# Trace.net
KiCad netlist of a schematic drawn in EAGLE
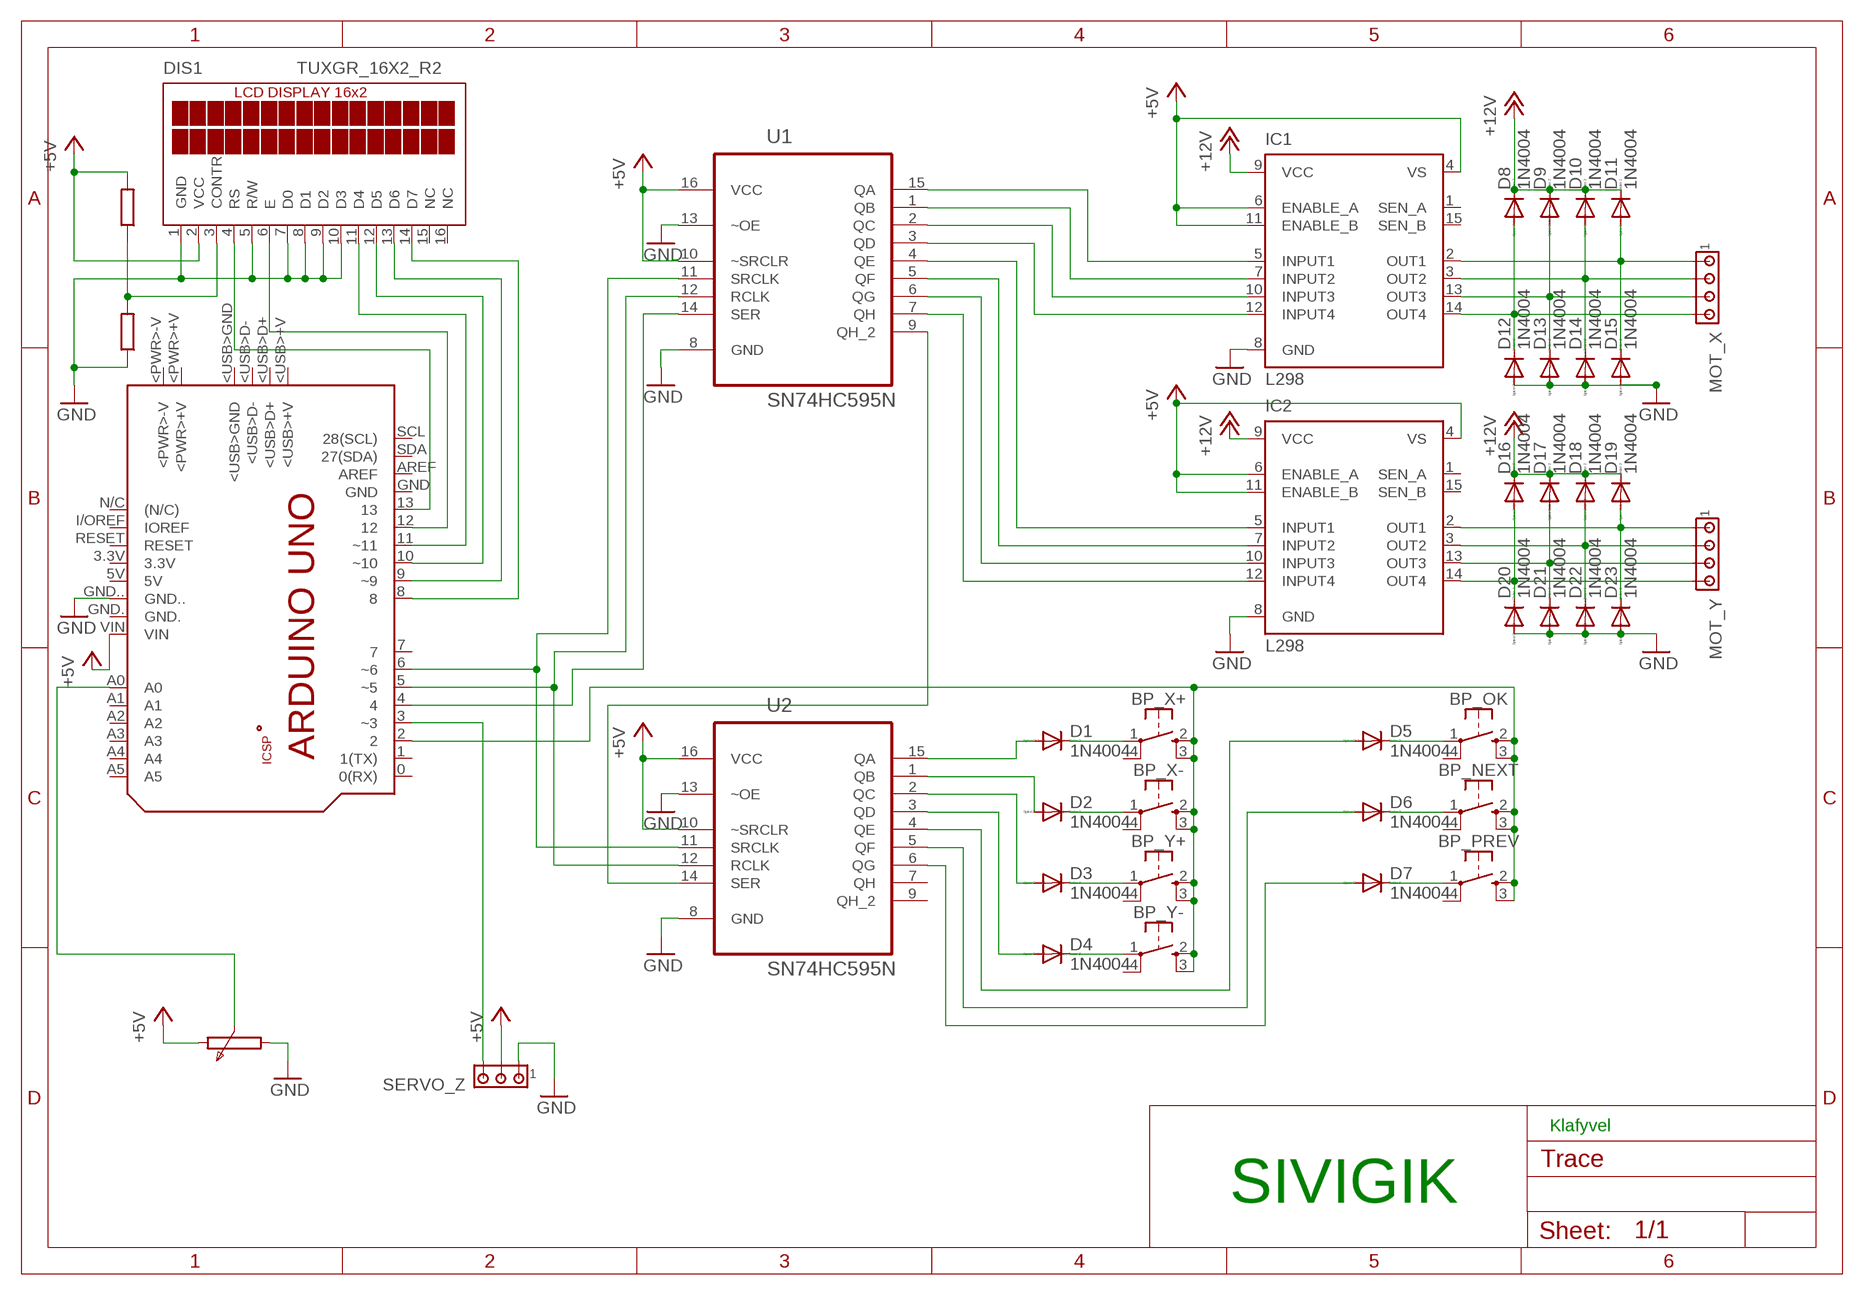
[diagram p0: schematic, sheet 1]

(export (version "E")
  (design (tool "Eeschema 10.0.6"))
  (components
    (comp (ref "BP_NEXT")
      (value "SW-TACTILE-TL3315")
      (footprint "eagle-import:SW_TL3315N")
      (libsource (lib "eagle-import") (part "SW-TACTILE-TL3315"))
    )
    (comp (ref "BP_OK")
      (value "SW-TACTILE-TL3315")
      (footprint "eagle-import:SW_TL3315N")
      (libsource (lib "eagle-import") (part "SW-TACTILE-TL3315"))
    )
    (comp (ref "BP_PREV")
      (value "SW-TACTILE-TL3315")
      (footprint "eagle-import:SW_TL3315N")
      (libsource (lib "eagle-import") (part "SW-TACTILE-TL3315"))
    )
    (comp (ref "BP_X+")
      (value "SW-TACTILE-TL3315")
      (footprint "eagle-import:SW_TL3315N")
      (libsource (lib "eagle-import") (part "SW-TACTILE-TL3315"))
    )
    (comp (ref "BP_X-")
      (value "SW-TACTILE-TL3315")
      (footprint "eagle-import:SW_TL3315N")
      (libsource (lib "eagle-import") (part "SW-TACTILE-TL3315"))
    )
    (comp (ref "BP_Y+")
      (value "SW-TACTILE-TL3315")
      (footprint "eagle-import:SW_TL3315N")
      (libsource (lib "eagle-import") (part "SW-TACTILE-TL3315"))
    )
    (comp (ref "BP_Y-")
      (value "SW-TACTILE-TL3315")
      (footprint "eagle-import:SW_TL3315N")
      (libsource (lib "eagle-import") (part "SW-TACTILE-TL3315"))
    )
    (comp (ref "D1")
      (value "1N4004")
      (footprint "eagle-import:DO41-10")
      (libsource (lib "eagle-import") (part "1N4004"))
    )
    (comp (ref "D2")
      (value "1N4004")
      (footprint "eagle-import:DO41-10")
      (libsource (lib "eagle-import") (part "1N4004"))
    )
    (comp (ref "D3")
      (value "1N4004")
      (footprint "eagle-import:DO41-10")
      (libsource (lib "eagle-import") (part "1N4004"))
    )
    (comp (ref "D4")
      (value "1N4004")
      (footprint "eagle-import:DO41-10")
      (libsource (lib "eagle-import") (part "1N4004"))
    )
    (comp (ref "D5")
      (value "1N4004")
      (footprint "eagle-import:DO41-10")
      (libsource (lib "eagle-import") (part "1N4004"))
    )
    (comp (ref "D6")
      (value "1N4004")
      (footprint "eagle-import:DO41-10")
      (libsource (lib "eagle-import") (part "1N4004"))
    )
    (comp (ref "D7")
      (value "1N4004")
      (footprint "eagle-import:DO41-10")
      (libsource (lib "eagle-import") (part "1N4004"))
    )
    (comp (ref "D8")
      (value "1N4004")
      (footprint "eagle-import:DO41-10")
      (libsource (lib "eagle-import") (part "1N4004"))
    )
    (comp (ref "D9")
      (value "1N4004")
      (footprint "eagle-import:DO41-10")
      (libsource (lib "eagle-import") (part "1N4004"))
    )
    (comp (ref "D10")
      (value "1N4004")
      (footprint "eagle-import:DO41-10")
      (libsource (lib "eagle-import") (part "1N4004"))
    )
    (comp (ref "D11")
      (value "1N4004")
      (footprint "eagle-import:DO41-10")
      (libsource (lib "eagle-import") (part "1N4004"))
    )
    (comp (ref "D12")
      (value "1N4004")
      (footprint "eagle-import:DO41-10")
      (libsource (lib "eagle-import") (part "1N4004"))
    )
    (comp (ref "D13")
      (value "1N4004")
      (footprint "eagle-import:DO41-10")
      (libsource (lib "eagle-import") (part "1N4004"))
    )
    (comp (ref "D14")
      (value "1N4004")
      (footprint "eagle-import:DO41-10")
      (libsource (lib "eagle-import") (part "1N4004"))
    )
    (comp (ref "D15")
      (value "1N4004")
      (footprint "eagle-import:DO41-10")
      (libsource (lib "eagle-import") (part "1N4004"))
    )
    (comp (ref "D16")
      (value "1N4004")
      (footprint "eagle-import:DO41-10")
      (libsource (lib "eagle-import") (part "1N4004"))
    )
    (comp (ref "D17")
      (value "1N4004")
      (footprint "eagle-import:DO41-10")
      (libsource (lib "eagle-import") (part "1N4004"))
    )
    (comp (ref "D18")
      (value "1N4004")
      (footprint "eagle-import:DO41-10")
      (libsource (lib "eagle-import") (part "1N4004"))
    )
    (comp (ref "D19")
      (value "1N4004")
      (footprint "eagle-import:DO41-10")
      (libsource (lib "eagle-import") (part "1N4004"))
    )
    (comp (ref "D20")
      (value "1N4004")
      (footprint "eagle-import:DO41-10")
      (libsource (lib "eagle-import") (part "1N4004"))
    )
    (comp (ref "D21")
      (value "1N4004")
      (footprint "eagle-import:DO41-10")
      (libsource (lib "eagle-import") (part "1N4004"))
    )
    (comp (ref "D22")
      (value "1N4004")
      (footprint "eagle-import:DO41-10")
      (libsource (lib "eagle-import") (part "1N4004"))
    )
    (comp (ref "D23")
      (value "1N4004")
      (footprint "eagle-import:DO41-10")
      (libsource (lib "eagle-import") (part "1N4004"))
    )
    (comp (ref "DIS1")
      (value "TUXGR_16X2_R2")
      (footprint "eagle-import:TUXGR_16X2_R2")
      (libsource (lib "eagle-import") (part "TUXGR_16X2_R2"))
    )
    (comp (ref "IC1")
      (value "L298")
      (footprint "eagle-import:MULTIWATT-15")
      (fields (field (name "MPN") "L298N"))
      (libsource (lib "eagle-import") (part "L298"))
    )
    (comp (ref "IC2")
      (value "L298")
      (footprint "eagle-import:MULTIWATT-15")
      (fields (field (name "MPN") "L298N"))
      (libsource (lib "eagle-import") (part "L298"))
    )
    (comp (ref "MOT_X")
      (value "MTA04-100")
      (footprint "eagle-import:10X04MTA")
      (libsource (lib "eagle-import") (part "MTA04-100"))
    )
    (comp (ref "MOT_Y")
      (value "MTA04-100")
      (footprint "eagle-import:10X04MTA")
      (libsource (lib "eagle-import") (part "MTA04-100"))
    )
    (comp (ref "PCB1")
      (value "ARDUINO_UNO")
      (footprint "eagle-import:ARDUINO_UNO")
      (libsource (lib "eagle-import") (part "ARDUINO_UNO"))
    )
    (comp (ref "SERVO_Z")
      (value "MTA03-100")
      (footprint "eagle-import:10X03MTA")
      (libsource (lib "eagle-import") (part "MTA03-100"))
    )
    (comp (ref "U1")
      (value "SN74HC595N")
      (footprint "eagle-import:DIP254P762X508-16")
      (libsource (lib "eagle-import") (part "SN74HC595N"))
    )
    (comp (ref "U2")
      (value "SN74HC595N")
      (footprint "eagle-import:DIP254P762X508-16")
      (libsource (lib "eagle-import") (part "SN74HC595N"))
    )
  )
  (nets
    (net (code "1") (name "+5V") (class "Default")
      (node (ref "DIS1") (pin "2") (pinfunction "VCC_2") (pintype "power_in"))
      (node (ref "IC1") (pin "11") (pinfunction "ENABLE_B_11") (pintype "input"))
      (node (ref "IC1") (pin "4") (pinfunction "VS_4") (pintype "power_in"))
      (node (ref "IC1") (pin "6") (pinfunction "ENABLE_A_6") (pintype "input"))
      (node (ref "IC2") (pin "11") (pinfunction "ENABLE_B_11") (pintype "input"))
      (node (ref "IC2") (pin "4") (pinfunction "VS_4") (pintype "power_in"))
      (node (ref "IC2") (pin "6") (pinfunction "ENABLE_A_6") (pintype "input"))
      (node (ref "PCB1") (pin "VIN") (pinfunction "VIN_VIN") (pintype "bidirectional"))
      (node (ref "SERVO_Z") (pin "2") (pinfunction "2_2") (pintype "passive"))
      (node (ref "U1") (pin "10") (pinfunction "~{SRCLR}_10") (pintype "input"))
      (node (ref "U1") (pin "16") (pinfunction "VCC_16") (pintype "power_in"))
      (node (ref "U2") (pin "10") (pinfunction "~{SRCLR}_10") (pintype "input"))
      (node (ref "U2") (pin "16") (pinfunction "VCC_16") (pintype "power_in"))
    )
    (net (code "2") (name "+12V") (class "Default")
      (node (ref "D10") (pin "C") (pinfunction "C_C") (pintype "passive"))
      (node (ref "D11") (pin "C") (pinfunction "C_C") (pintype "passive"))
      (node (ref "D16") (pin "C") (pinfunction "C_C") (pintype "passive"))
      (node (ref "D17") (pin "C") (pinfunction "C_C") (pintype "passive"))
      (node (ref "D18") (pin "C") (pinfunction "C_C") (pintype "passive"))
      (node (ref "D19") (pin "C") (pinfunction "C_C") (pintype "passive"))
      (node (ref "D8") (pin "C") (pinfunction "C_C") (pintype "passive"))
      (node (ref "D9") (pin "C") (pinfunction "C_C") (pintype "passive"))
      (node (ref "IC1") (pin "9") (pinfunction "VCC_9") (pintype "power_in"))
      (node (ref "IC2") (pin "9") (pinfunction "VCC_9") (pintype "power_in"))
    )
    (net (code "3") (name "GND") (class "Default")
      (node (ref "D12") (pin "A") (pinfunction "A_A") (pintype "passive"))
      (node (ref "D13") (pin "A") (pinfunction "A_A") (pintype "passive"))
      (node (ref "D14") (pin "A") (pinfunction "A_A") (pintype "passive"))
      (node (ref "D15") (pin "A") (pinfunction "A_A") (pintype "passive"))
      (node (ref "D20") (pin "A") (pinfunction "A_A") (pintype "passive"))
      (node (ref "D21") (pin "A") (pinfunction "A_A") (pintype "passive"))
      (node (ref "D22") (pin "A") (pinfunction "A_A") (pintype "passive"))
      (node (ref "D23") (pin "A") (pinfunction "A_A") (pintype "passive"))
      (node (ref "DIS1") (pin "1") (pinfunction "GND_1") (pintype "power_in"))
      (node (ref "DIS1") (pin "10") (pinfunction "D3_10") (pintype "input"))
      (node (ref "DIS1") (pin "5") (pinfunction "R/W_5") (pintype "input"))
      (node (ref "DIS1") (pin "7") (pinfunction "D0_7") (pintype "input"))
      (node (ref "DIS1") (pin "8") (pinfunction "D1_8") (pintype "input"))
      (node (ref "DIS1") (pin "9") (pinfunction "D2_9") (pintype "input"))
      (node (ref "IC1") (pin "8") (pinfunction "GND_8") (pintype "power_in"))
      (node (ref "IC2") (pin "8") (pinfunction "GND_8") (pintype "power_in"))
      (node (ref "PCB1") (pin "GND..") (pinfunction "GND.._GND..") (pintype "bidirectional"))
      (node (ref "SERVO_Z") (pin "1") (pinfunction "1_1") (pintype "passive"))
      (node (ref "U1") (pin "13") (pinfunction "~{OE}_13") (pintype "input"))
      (node (ref "U1") (pin "8") (pinfunction "GND_8") (pintype "passive"))
      (node (ref "U2") (pin "13") (pinfunction "~{OE}_13") (pintype "input"))
      (node (ref "U2") (pin "8") (pinfunction "GND_8") (pintype "passive"))
    )
    (net (code "4") (name "Net-(BP_NEXT-P1)") (class "Default")
      (node (ref "BP_NEXT") (pin "1") (pinfunction "P1_1") (pintype "passive"))
      (node (ref "D6") (pin "C") (pinfunction "C_C") (pintype "passive"))
    )
    (net (code "5") (name "Net-(BP_NEXT-S1)") (class "Default")
      (node (ref "BP_NEXT") (pin "2") (pinfunction "S1_2") (pintype "passive"))
      (node (ref "BP_NEXT") (pin "3") (pinfunction "S2_3") (pintype "passive"))
      (node (ref "BP_OK") (pin "2") (pinfunction "S1_2") (pintype "passive"))
      (node (ref "BP_OK") (pin "3") (pinfunction "S2_3") (pintype "passive"))
      (node (ref "BP_PREV") (pin "2") (pinfunction "S1_2") (pintype "passive"))
      (node (ref "BP_PREV") (pin "3") (pinfunction "S2_3") (pintype "passive"))
      (node (ref "BP_X+") (pin "2") (pinfunction "S1_2") (pintype "passive"))
      (node (ref "BP_X+") (pin "3") (pinfunction "S2_3") (pintype "passive"))
      (node (ref "BP_X-") (pin "2") (pinfunction "S1_2") (pintype "passive"))
      (node (ref "BP_X-") (pin "3") (pinfunction "S2_3") (pintype "passive"))
      (node (ref "BP_Y+") (pin "2") (pinfunction "S1_2") (pintype "passive"))
      (node (ref "BP_Y+") (pin "3") (pinfunction "S2_3") (pintype "passive"))
      (node (ref "BP_Y-") (pin "2") (pinfunction "S1_2") (pintype "passive"))
      (node (ref "BP_Y-") (pin "3") (pinfunction "S2_3") (pintype "passive"))
      (node (ref "PCB1") (pin "2") (pinfunction "2_2") (pintype "bidirectional"))
    )
    (net (code "6") (name "Net-(BP_OK-P1)") (class "Default")
      (node (ref "BP_OK") (pin "1") (pinfunction "P1_1") (pintype "passive"))
      (node (ref "D5") (pin "C") (pinfunction "C_C") (pintype "passive"))
    )
    (net (code "7") (name "Net-(BP_PREV-P1)") (class "Default")
      (node (ref "BP_PREV") (pin "1") (pinfunction "P1_1") (pintype "passive"))
      (node (ref "D7") (pin "C") (pinfunction "C_C") (pintype "passive"))
    )
    (net (code "8") (name "Net-(BP_X+-P1)") (class "Default")
      (node (ref "BP_X+") (pin "1") (pinfunction "P1_1") (pintype "passive"))
      (node (ref "D1") (pin "C") (pinfunction "C_C") (pintype "passive"))
    )
    (net (code "9") (name "Net-(BP_X--P1)") (class "Default")
      (node (ref "BP_X-") (pin "1") (pinfunction "P1_1") (pintype "passive"))
      (node (ref "D2") (pin "C") (pinfunction "C_C") (pintype "passive"))
    )
    (net (code "10") (name "Net-(BP_Y+-P1)") (class "Default")
      (node (ref "BP_Y+") (pin "1") (pinfunction "P1_1") (pintype "passive"))
      (node (ref "D3") (pin "C") (pinfunction "C_C") (pintype "passive"))
    )
    (net (code "11") (name "Net-(BP_Y--P1)") (class "Default")
      (node (ref "BP_Y-") (pin "1") (pinfunction "P1_1") (pintype "passive"))
      (node (ref "D4") (pin "C") (pinfunction "C_C") (pintype "passive"))
    )
    (net (code "12") (name "Net-(DIS1-D4)") (class "Default")
      (node (ref "DIS1") (pin "11") (pinfunction "D4_11") (pintype "input"))
      (node (ref "PCB1") (pin "11") (pinfunction "~{11}_11") (pintype "bidirectional"))
    )
    (net (code "13") (name "Net-(DIS1-D5)") (class "Default")
      (node (ref "DIS1") (pin "12") (pinfunction "D5_12") (pintype "input"))
      (node (ref "PCB1") (pin "10") (pinfunction "~{10}_10") (pintype "bidirectional"))
    )
    (net (code "14") (name "Net-(DIS1-D6)") (class "Default")
      (node (ref "DIS1") (pin "13") (pinfunction "D6_13") (pintype "input"))
      (node (ref "PCB1") (pin "9") (pinfunction "~{9}_9") (pintype "bidirectional"))
    )
    (net (code "15") (name "Net-(DIS1-D7)") (class "Default")
      (node (ref "DIS1") (pin "14") (pinfunction "D7_14") (pintype "input"))
      (node (ref "PCB1") (pin "8") (pinfunction "8_8") (pintype "bidirectional"))
    )
    (net (code "16") (name "Net-(DIS1-E)") (class "Default")
      (node (ref "DIS1") (pin "6") (pinfunction "E_6") (pintype "input"))
      (node (ref "PCB1") (pin "12") (pinfunction "12_12") (pintype "bidirectional"))
    )
    (net (code "17") (name "Net-(DIS1-RS)") (class "Default")
      (node (ref "DIS1") (pin "4") (pinfunction "RS_4") (pintype "input"))
      (node (ref "PCB1") (pin "13") (pinfunction "13_13") (pintype "bidirectional"))
    )
    (net (code "18") (name "Net-(IC1-INPUT1)") (class "Default")
      (node (ref "IC1") (pin "5") (pinfunction "INPUT1_5") (pintype "input"))
      (node (ref "U1") (pin "15") (pinfunction "QA_15") (pintype "output"))
    )
    (net (code "19") (name "Net-(IC1-INPUT2)") (class "Default")
      (node (ref "IC1") (pin "7") (pinfunction "INPUT2_7") (pintype "input"))
      (node (ref "U1") (pin "1") (pinfunction "QB_1") (pintype "output"))
    )
    (net (code "20") (name "Net-(IC1-INPUT3)") (class "Default")
      (node (ref "IC1") (pin "10") (pinfunction "INPUT3_10") (pintype "input"))
      (node (ref "U1") (pin "2") (pinfunction "QC_2") (pintype "output"))
    )
    (net (code "21") (name "Net-(IC1-INPUT4)") (class "Default")
      (node (ref "IC1") (pin "12") (pinfunction "INPUT4_12") (pintype "input"))
      (node (ref "U1") (pin "3") (pinfunction "QD_3") (pintype "output"))
    )
    (net (code "22") (name "Net-(IC1-OUT1)") (class "Default")
      (node (ref "D11") (pin "A") (pinfunction "A_A") (pintype "passive"))
      (node (ref "D15") (pin "C") (pinfunction "C_C") (pintype "passive"))
      (node (ref "IC1") (pin "2") (pinfunction "OUT1_2") (pintype "output"))
      (node (ref "MOT_X") (pin "1") (pinfunction "1_1") (pintype "passive"))
    )
    (net (code "23") (name "Net-(IC1-OUT2)") (class "Default")
      (node (ref "D10") (pin "A") (pinfunction "A_A") (pintype "passive"))
      (node (ref "D14") (pin "C") (pinfunction "C_C") (pintype "passive"))
      (node (ref "IC1") (pin "3") (pinfunction "OUT2_3") (pintype "output"))
      (node (ref "MOT_X") (pin "2") (pinfunction "2_2") (pintype "passive"))
    )
    (net (code "24") (name "Net-(IC1-OUT3)") (class "Default")
      (node (ref "D13") (pin "C") (pinfunction "C_C") (pintype "passive"))
      (node (ref "D9") (pin "A") (pinfunction "A_A") (pintype "passive"))
      (node (ref "IC1") (pin "13") (pinfunction "OUT3_13") (pintype "output"))
      (node (ref "MOT_X") (pin "3") (pinfunction "3_3") (pintype "passive"))
    )
    (net (code "25") (name "Net-(IC1-OUT4)") (class "Default")
      (node (ref "D12") (pin "C") (pinfunction "C_C") (pintype "passive"))
      (node (ref "D8") (pin "A") (pinfunction "A_A") (pintype "passive"))
      (node (ref "IC1") (pin "14") (pinfunction "OUT4_14") (pintype "output"))
      (node (ref "MOT_X") (pin "4") (pinfunction "4_4") (pintype "passive"))
    )
    (net (code "26") (name "Net-(IC2-INPUT1)") (class "Default")
      (node (ref "IC2") (pin "5") (pinfunction "INPUT1_5") (pintype "input"))
      (node (ref "U1") (pin "4") (pinfunction "QE_4") (pintype "output"))
    )
    (net (code "27") (name "Net-(IC2-INPUT2)") (class "Default")
      (node (ref "IC2") (pin "7") (pinfunction "INPUT2_7") (pintype "input"))
      (node (ref "U1") (pin "5") (pinfunction "QF_5") (pintype "output"))
    )
    (net (code "28") (name "Net-(IC2-INPUT3)") (class "Default")
      (node (ref "IC2") (pin "10") (pinfunction "INPUT3_10") (pintype "input"))
      (node (ref "U1") (pin "6") (pinfunction "QG_6") (pintype "output"))
    )
    (net (code "29") (name "Net-(IC2-INPUT4)") (class "Default")
      (node (ref "IC2") (pin "12") (pinfunction "INPUT4_12") (pintype "input"))
      (node (ref "U1") (pin "7") (pinfunction "QH_7") (pintype "output"))
    )
    (net (code "30") (name "Net-(IC2-OUT1)") (class "Default")
      (node (ref "D19") (pin "A") (pinfunction "A_A") (pintype "passive"))
      (node (ref "D23") (pin "C") (pinfunction "C_C") (pintype "passive"))
      (node (ref "IC2") (pin "2") (pinfunction "OUT1_2") (pintype "output"))
      (node (ref "MOT_Y") (pin "1") (pinfunction "1_1") (pintype "passive"))
    )
    (net (code "31") (name "Net-(IC2-OUT2)") (class "Default")
      (node (ref "D18") (pin "A") (pinfunction "A_A") (pintype "passive"))
      (node (ref "D22") (pin "C") (pinfunction "C_C") (pintype "passive"))
      (node (ref "IC2") (pin "3") (pinfunction "OUT2_3") (pintype "output"))
      (node (ref "MOT_Y") (pin "2") (pinfunction "2_2") (pintype "passive"))
    )
    (net (code "32") (name "Net-(IC2-OUT3)") (class "Default")
      (node (ref "D17") (pin "A") (pinfunction "A_A") (pintype "passive"))
      (node (ref "D21") (pin "C") (pinfunction "C_C") (pintype "passive"))
      (node (ref "IC2") (pin "13") (pinfunction "OUT3_13") (pintype "output"))
      (node (ref "MOT_Y") (pin "3") (pinfunction "3_3") (pintype "passive"))
    )
    (net (code "33") (name "Net-(IC2-OUT4)") (class "Default")
      (node (ref "D16") (pin "A") (pinfunction "A_A") (pintype "passive"))
      (node (ref "D20") (pin "C") (pinfunction "C_C") (pintype "passive"))
      (node (ref "IC2") (pin "14") (pinfunction "OUT4_14") (pintype "output"))
      (node (ref "MOT_Y") (pin "4") (pinfunction "4_4") (pintype "passive"))
    )
    (net (code "34") (name "Net-(PCB1-~{3})") (class "Default")
      (node (ref "PCB1") (pin "3") (pinfunction "~{3}_3") (pintype "bidirectional"))
      (node (ref "SERVO_Z") (pin "3") (pinfunction "3_3") (pintype "passive"))
    )
    (net (code "35") (name "Net-(PCB1-~{5})") (class "Default")
      (node (ref "PCB1") (pin "5") (pinfunction "~{5}_5") (pintype "bidirectional"))
      (node (ref "U1") (pin "12") (pinfunction "RCLK_12") (pintype "input"))
      (node (ref "U2") (pin "12") (pinfunction "RCLK_12") (pintype "input"))
    )
    (net (code "36") (name "Net-(PCB1-~{6})") (class "Default")
      (node (ref "PCB1") (pin "6") (pinfunction "~{6}_6") (pintype "bidirectional"))
      (node (ref "U1") (pin "11") (pinfunction "SRCLK_11") (pintype "input"))
      (node (ref "U2") (pin "11") (pinfunction "SRCLK_11") (pintype "input"))
    )
    (net (code "37") (name "Net-(U1-QH_2)") (class "Default")
      (node (ref "U1") (pin "9") (pinfunction "QH_2_9") (pintype "output"))
      (node (ref "U2") (pin "14") (pinfunction "SER_14") (pintype "input"))
    )
    (net (code "38") (name "Net-(U1-SER)") (class "Default")
      (node (ref "PCB1") (pin "4") (pinfunction "4_4") (pintype "bidirectional"))
      (node (ref "U1") (pin "14") (pinfunction "SER_14") (pintype "input"))
    )
    (net (code "39") (name "Net-(U2-QA)") (class "Default")
      (node (ref "D1") (pin "A") (pinfunction "A_A") (pintype "passive"))
      (node (ref "U2") (pin "15") (pinfunction "QA_15") (pintype "output"))
    )
    (net (code "40") (name "Net-(U2-QB)") (class "Default")
      (node (ref "D2") (pin "A") (pinfunction "A_A") (pintype "passive"))
      (node (ref "U2") (pin "1") (pinfunction "QB_1") (pintype "output"))
    )
    (net (code "41") (name "Net-(U2-QC)") (class "Default")
      (node (ref "D3") (pin "A") (pinfunction "A_A") (pintype "passive"))
      (node (ref "U2") (pin "2") (pinfunction "QC_2") (pintype "output"))
    )
    (net (code "42") (name "Net-(U2-QD)") (class "Default")
      (node (ref "D4") (pin "A") (pinfunction "A_A") (pintype "passive"))
      (node (ref "U2") (pin "3") (pinfunction "QD_3") (pintype "output"))
    )
    (net (code "43") (name "Net-(U2-QE)") (class "Default")
      (node (ref "D5") (pin "A") (pinfunction "A_A") (pintype "passive"))
      (node (ref "U2") (pin "4") (pinfunction "QE_4") (pintype "output"))
    )
    (net (code "44") (name "Net-(U2-QF)") (class "Default")
      (node (ref "D6") (pin "A") (pinfunction "A_A") (pintype "passive"))
      (node (ref "U2") (pin "5") (pinfunction "QF_5") (pintype "output"))
    )
    (net (code "45") (name "Net-(U2-QG)") (class "Default")
      (node (ref "D7") (pin "A") (pinfunction "A_A") (pintype "passive"))
      (node (ref "U2") (pin "6") (pinfunction "QG_6") (pintype "output"))
    )
    (net (code "46") (name "unconnected-(BP_NEXT-P2-Pad4)") (class "Default")
      (node (ref "BP_NEXT") (pin "4") (pinfunction "P2_4") (pintype "passive"))
    )
    (net (code "47") (name "unconnected-(BP_OK-P2-Pad4)") (class "Default")
      (node (ref "BP_OK") (pin "4") (pinfunction "P2_4") (pintype "passive"))
    )
    (net (code "48") (name "unconnected-(BP_PREV-P2-Pad4)") (class "Default")
      (node (ref "BP_PREV") (pin "4") (pinfunction "P2_4") (pintype "passive"))
    )
    (net (code "49") (name "unconnected-(BP_X+-P2-Pad4)") (class "Default")
      (node (ref "BP_X+") (pin "4") (pinfunction "P2_4") (pintype "passive"))
    )
    (net (code "50") (name "unconnected-(BP_X--P2-Pad4)") (class "Default")
      (node (ref "BP_X-") (pin "4") (pinfunction "P2_4") (pintype "passive"))
    )
    (net (code "51") (name "unconnected-(BP_Y+-P2-Pad4)") (class "Default")
      (node (ref "BP_Y+") (pin "4") (pinfunction "P2_4") (pintype "passive"))
    )
    (net (code "52") (name "unconnected-(BP_Y--P2-Pad4)") (class "Default")
      (node (ref "BP_Y-") (pin "4") (pinfunction "P2_4") (pintype "passive"))
    )
    (net (code "53") (name "unconnected-(DIS1-CONTR-Pad3)") (class "Default")
      (node (ref "DIS1") (pin "3") (pinfunction "CONTR_3") (pintype "input"))
    )
    (net (code "54") (name "unconnected-(DIS1-NC-Pad15)") (class "Default")
      (node (ref "DIS1") (pin "15") (pinfunction "NC_15") (pintype "no_connect"))
    )
    (net (code "55") (name "unconnected-(DIS1-NC-Pad16)") (class "Default")
      (node (ref "DIS1") (pin "16") (pinfunction "NC_16") (pintype "no_connect"))
    )
    (net (code "56") (name "unconnected-(IC1-SEN_A-Pad1)") (class "Default")
      (node (ref "IC1") (pin "1") (pinfunction "SEN_A_1") (pintype "input"))
    )
    (net (code "57") (name "unconnected-(IC1-SEN_B-Pad15)") (class "Default")
      (node (ref "IC1") (pin "15") (pinfunction "SEN_B_15") (pintype "input"))
    )
    (net (code "58") (name "unconnected-(IC2-SEN_A-Pad1)") (class "Default")
      (node (ref "IC2") (pin "1") (pinfunction "SEN_A_1") (pintype "input"))
    )
    (net (code "59") (name "unconnected-(IC2-SEN_B-Pad15)") (class "Default")
      (node (ref "IC2") (pin "15") (pinfunction "SEN_B_15") (pintype "input"))
    )
    (net (code "60") (name "unconnected-(PCB1-(N{slash}C)-PadN{slash}C)") (class "Default")
      (node (ref "PCB1") (pin "N/C") (pinfunction "(N/C)_N/C") (pintype "bidirectional"))
    )
    (net (code "61") (name "unconnected-(PCB1-0(RX)-Pad0)") (class "Default")
      (node (ref "PCB1") (pin "0") (pinfunction "0(RX)_0") (pintype "bidirectional"))
    )
    (net (code "62") (name "unconnected-(PCB1-1(TX)-Pad1)") (class "Default")
      (node (ref "PCB1") (pin "1") (pinfunction "1(TX)_1") (pintype "bidirectional"))
    )
    (net (code "63") (name "unconnected-(PCB1-27(SDA)-PadSDA)") (class "Default")
      (node (ref "PCB1") (pin "SDA") (pinfunction "27(SDA)_SDA") (pintype "bidirectional"))
    )
    (net (code "64") (name "unconnected-(PCB1-28(SCL)-PadSCL)") (class "Default")
      (node (ref "PCB1") (pin "SCL") (pinfunction "28(SCL)_SCL") (pintype "bidirectional"))
    )
    (net (code "65") (name "unconnected-(PCB1-IOREF-PadI{slash}OREF)") (class "Default")
      (node (ref "PCB1") (pin "I/OREF") (pinfunction "IOREF_I/OREF") (pintype "bidirectional"))
    )
    (net (code "66") (name "unconnected-(PCB1-Pad+5V)") (class "Default")
      (node (ref "PCB1") (pin "+5V") (pinfunction "+5V_+5V") (pintype "bidirectional"))
    )
    (net (code "67") (name "unconnected-(PCB1-Pad3.3V)") (class "Default")
      (node (ref "PCB1") (pin "3.3V") (pinfunction "3.3V_3.3V") (pintype "bidirectional"))
    )
    (net (code "68") (name "unconnected-(PCB1-Pad5V)") (class "Default")
      (node (ref "PCB1") (pin "5V") (pinfunction "5V_5V") (pintype "bidirectional"))
    )
    (net (code "69") (name "unconnected-(PCB1-Pad7)") (class "Default")
      (node (ref "PCB1") (pin "7") (pinfunction "7_7") (pintype "bidirectional"))
    )
    (net (code "70") (name "unconnected-(PCB1-Pad<PWR>+V)") (class "Default")
      (node (ref "PCB1") (pin "<PWR>+V") (pinfunction "<PWR>+V_<PWR>+V") (pintype "bidirectional"))
    )
    (net (code "71") (name "unconnected-(PCB1-Pad<PWR>-V)") (class "Default")
      (node (ref "PCB1") (pin "<PWR>-V") (pinfunction "<PWR>-V_<PWR>-V") (pintype "bidirectional"))
    )
    (net (code "72") (name "unconnected-(PCB1-Pad<USB>+V)") (class "Default")
      (node (ref "PCB1") (pin "<USB>+V") (pinfunction "<USB>+V_<USB>+V") (pintype "bidirectional"))
    )
    (net (code "73") (name "unconnected-(PCB1-Pad<USB>D+)") (class "Default")
      (node (ref "PCB1") (pin "<USB>D+") (pinfunction "<USB>D+_<USB>D+") (pintype "bidirectional"))
    )
    (net (code "74") (name "unconnected-(PCB1-Pad<USB>D-)") (class "Default")
      (node (ref "PCB1") (pin "<USB>D-") (pinfunction "<USB>D-_<USB>D-") (pintype "bidirectional"))
    )
    (net (code "75") (name "unconnected-(PCB1-Pad<USB>GND)") (class "Default")
      (node (ref "PCB1") (pin "<USB>GND") (pinfunction "<USB>GND_<USB>GND") (pintype "bidirectional"))
    )
    (net (code "76") (name "unconnected-(PCB1-PadA0)") (class "Default")
      (node (ref "PCB1") (pin "A0") (pinfunction "A0_A0") (pintype "bidirectional"))
    )
    (net (code "77") (name "unconnected-(PCB1-PadA1)") (class "Default")
      (node (ref "PCB1") (pin "A1") (pinfunction "A1_A1") (pintype "bidirectional"))
    )
    (net (code "78") (name "unconnected-(PCB1-PadA2)") (class "Default")
      (node (ref "PCB1") (pin "A2") (pinfunction "A2_A2") (pintype "bidirectional"))
    )
    (net (code "79") (name "unconnected-(PCB1-PadA3)") (class "Default")
      (node (ref "PCB1") (pin "A3") (pinfunction "A3_A3") (pintype "bidirectional"))
    )
    (net (code "80") (name "unconnected-(PCB1-PadA4)") (class "Default")
      (node (ref "PCB1") (pin "A4") (pinfunction "A4_A4") (pintype "bidirectional"))
    )
    (net (code "81") (name "unconnected-(PCB1-PadA5)") (class "Default")
      (node (ref "PCB1") (pin "A5") (pinfunction "A5_A5") (pintype "bidirectional"))
    )
    (net (code "82") (name "unconnected-(PCB1-PadAREF)") (class "Default")
      (node (ref "PCB1") (pin "AREF") (pinfunction "AREF_AREF") (pintype "bidirectional"))
    )
    (net (code "83") (name "unconnected-(PCB1-PadGND)") (class "Default")
      (node (ref "PCB1") (pin "GND") (pinfunction "GND_GND") (pintype "bidirectional"))
    )
    (net (code "84") (name "unconnected-(PCB1-PadGND.)") (class "Default")
      (node (ref "PCB1") (pin "GND.") (pinfunction "GND._GND.") (pintype "bidirectional"))
    )
    (net (code "85") (name "unconnected-(PCB1-PadGND_)") (class "Default")
      (node (ref "PCB1") (pin "GND_") (pinfunction "GND__GND_") (pintype "bidirectional"))
    )
    (net (code "86") (name "unconnected-(PCB1-PadMISO)") (class "Default")
      (node (ref "PCB1") (pin "MISO") (pinfunction "MISO_MISO") (pintype "bidirectional"))
    )
    (net (code "87") (name "unconnected-(PCB1-PadMOSI)") (class "Default")
      (node (ref "PCB1") (pin "MOSI") (pinfunction "MOSI_MOSI") (pintype "bidirectional"))
    )
    (net (code "88") (name "unconnected-(PCB1-PadRESET)") (class "Default")
      (node (ref "PCB1") (pin "RESET") (pinfunction "RESET_RESET") (pintype "bidirectional"))
    )
    (net (code "89") (name "unconnected-(PCB1-PadRESET.)") (class "Default")
      (node (ref "PCB1") (pin "RESET.") (pinfunction "RESET._RESET.") (pintype "bidirectional"))
    )
    (net (code "90") (name "unconnected-(PCB1-PadSCK)") (class "Default")
      (node (ref "PCB1") (pin "SCK") (pinfunction "SCK_SCK") (pintype "bidirectional"))
    )
    (net (code "91") (name "unconnected-(U2-QH-Pad7)") (class "Default")
      (node (ref "U2") (pin "7") (pinfunction "QH_7") (pintype "output"))
    )
    (net (code "92") (name "unconnected-(U2-QH_2-Pad9)") (class "Default")
      (node (ref "U2") (pin "9") (pinfunction "QH_2_9") (pintype "output"))
    )
  )
)
